# ESP32-C3_v1_0_Schematic.net
KiCad netlist of a schematic drawn in EAGLE
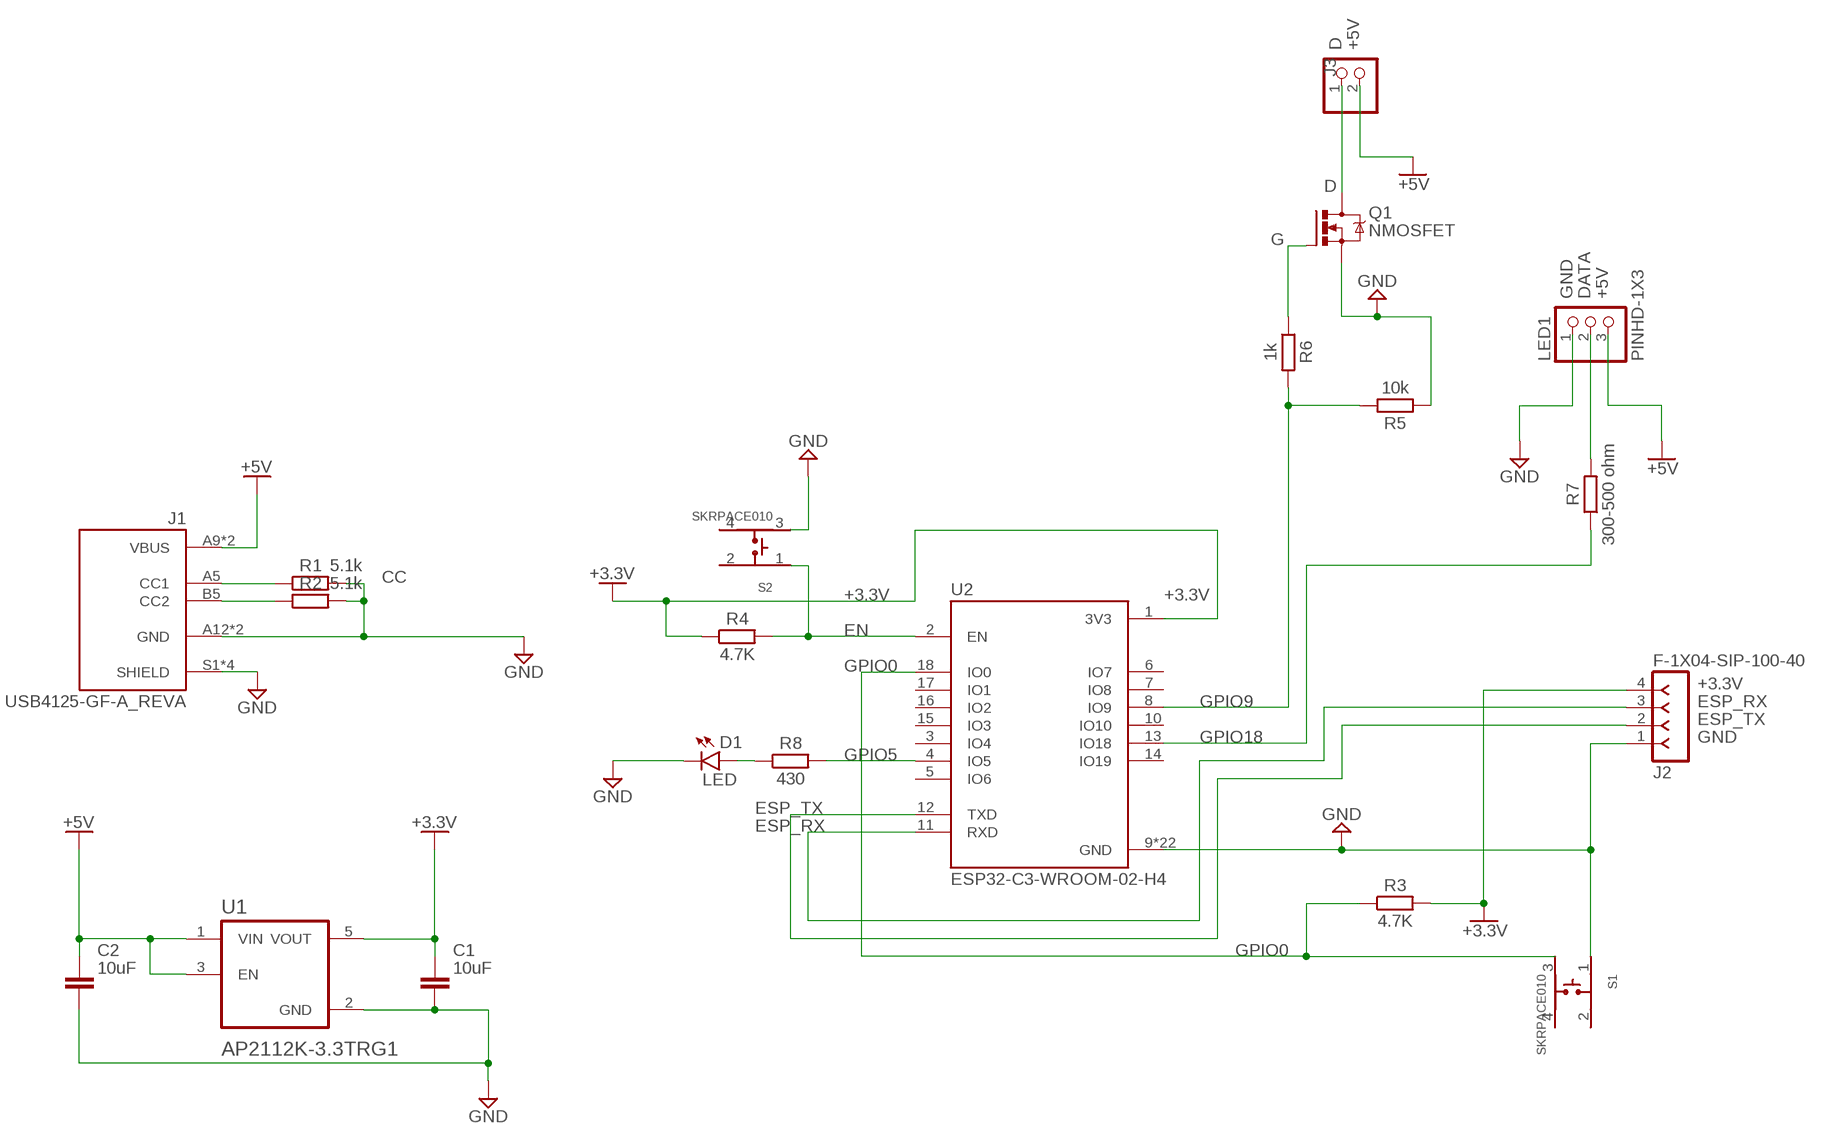
[diagram p0: schematic, sheet 1]

(export (version "E")
  (design (tool "Eeschema 10.0.6"))
  (components
    (comp (ref "C1")
      (value "10uF")
      (footprint "eagle-import:CAPC1608X85")
      (libsource (lib "eagle-import") (part "CCHIP-0603(1608-METRIC)_"))
    )
    (comp (ref "C2")
      (value "10uF")
      (footprint "eagle-import:CAPC1608X85")
      (libsource (lib "eagle-import") (part "CCHIP-0603(1608-METRIC)_"))
    )
    (comp (ref "D1")
      (value "LED")
      (footprint "eagle-import:LEDC1608X80N_FLAT-R")
      (libsource (lib "eagle-import") (part "CHIP-FLAT-R_0603-0.80MM"))
    )
    (comp (ref "J1")
      (value "USB4125-GF-A_REVA")
      (footprint "eagle-import:GCT_USB4125-GF-A_REVA")
      (fields (field (name "MF") "Global Connector Technology") (field (name "MP") "USB4125-GF-A"))
      (libsource (lib "eagle-import") (part "USB4125-GF-A_REVA"))
    )
    (comp (ref "J2")
      (value "F-1X04-SIP-100-40")
      (footprint "eagle-import:SIP-100-04-40")
      (libsource (lib "eagle-import") (part "F-1X04-SIP-100-40"))
    )
    (comp (ref "J3")
      (value "PINHD-1X2")
      (footprint "eagle-import:1X02")
      (libsource (lib "eagle-import") (part "PINHD-1X2"))
    )
    (comp (ref "LED1")
      (value "PINHD-1X3")
      (footprint "eagle-import:1X03")
      (libsource (lib "eagle-import") (part "PINHD-1X3"))
    )
    (comp (ref "Q1")
      (value "NMOSFET")
      (footprint "eagle-import:SOT23")
      (libsource (lib "eagle-import") (part "NMOSFETSOT23-GSD_"))
    )
    (comp (ref "R1")
      (value "5.1k")
      (footprint "eagle-import:RESC1608X60")
      (libsource (lib "eagle-import") (part "RCHIP-0603(1608-METRIC)_"))
    )
    (comp (ref "R2")
      (value "5.1k")
      (footprint "eagle-import:RESC1608X60")
      (libsource (lib "eagle-import") (part "RCHIP-0603(1608-METRIC)_"))
    )
    (comp (ref "R3")
      (value "4.7K")
      (footprint "eagle-import:RESC1608X60")
      (libsource (lib "eagle-import") (part "RCHIP-0603(1608-METRIC)_"))
    )
    (comp (ref "R4")
      (value "4.7K")
      (footprint "eagle-import:RESC1608X60")
      (libsource (lib "eagle-import") (part "RCHIP-0603(1608-METRIC)_"))
    )
    (comp (ref "R5")
      (value "10k")
      (footprint "eagle-import:RESC1608X60")
      (libsource (lib "eagle-import") (part "RCHIP-0603(1608-METRIC)_"))
    )
    (comp (ref "R6")
      (value "1k")
      (footprint "eagle-import:RESC1608X60")
      (libsource (lib "eagle-import") (part "RCHIP-0603(1608-METRIC)_"))
    )
    (comp (ref "R7")
      (value "300-500 ohm")
      (footprint "eagle-import:RESC1608X60")
      (libsource (lib "eagle-import") (part "RCHIP-0603(1608-METRIC)_"))
    )
    (comp (ref "R8")
      (value "430")
      (footprint "eagle-import:RESC1608X60")
      (libsource (lib "eagle-import") (part "RCHIP-0603(1608-METRIC)_"))
    )
    (comp (ref "S1")
      (value "SKRPACE010")
      (footprint "eagle-import:SW_SKRPACE010")
      (fields (field (name "MANUFACTURER") "ALPS"))
      (libsource (lib "eagle-import") (part "SKRPACE010"))
    )
    (comp (ref "S2")
      (value "SKRPACE010")
      (footprint "eagle-import:SW_SKRPACE010")
      (fields (field (name "MANUFACTURER") "ALPS"))
      (libsource (lib "eagle-import") (part "SKRPACE010"))
    )
    (comp (ref "U1")
      (value "AP2112K-3.3TRG1")
      (footprint "eagle-import:SOT95P285X140-5N")
      (fields (field (name "MANUFACTURER") "Diodes Inc."))
      (libsource (lib "eagle-import") (part "AP2112K-3.3TRG1"))
    )
    (comp (ref "U2")
      (value "ESP32-C3-WROOM-02-H4")
      (footprint "eagle-import:MODULE_ESP32-C3-WROOM-02-H4")
      (fields (field (name "MF") "Espressif Systems"))
      (libsource (lib "eagle-import") (part "ESP32-C3-WROOM-02-H4"))
    )
  )
  (nets
    (net (code "1") (name "+3.3V") (class "Default")
      (node (ref "C1") (pin "1") (pinfunction "1_1") (pintype "passive"))
      (node (ref "J2") (pin "4") (pinfunction "4_4") (pintype "passive"))
      (node (ref "R3") (pin "2") (pinfunction "2_2") (pintype "passive"))
      (node (ref "R4") (pin "1") (pinfunction "1_1") (pintype "passive"))
      (node (ref "U1") (pin "5") (pinfunction "VOUT_5") (pintype "power_in"))
      (node (ref "U2") (pin "1") (pinfunction "3V3_1") (pintype "power_in"))
    )
    (net (code "2") (name "+5V") (class "Default")
      (node (ref "C2") (pin "1") (pinfunction "1_1") (pintype "passive"))
      (node (ref "J1") (pin "A9") (pinfunction "VBUS_A9") (pintype "power_in"))
      (node (ref "J1") (pin "B9") (pinfunction "VBUS_B9") (pintype "power_in"))
      (node (ref "J3") (pin "2") (pinfunction "2_2") (pintype "passive"))
      (node (ref "LED1") (pin "3") (pinfunction "3_3") (pintype "passive"))
      (node (ref "U1") (pin "1") (pinfunction "VIN_1") (pintype "power_in"))
      (node (ref "U1") (pin "3") (pinfunction "EN_3") (pintype "input"))
    )
    (net (code "3") (name "/CC") (class "Default")
      (node (ref "J1") (pin "A5") (pinfunction "CC1_A5") (pintype "bidirectional"))
      (node (ref "R1") (pin "1") (pinfunction "1_1") (pintype "passive"))
    )
    (net (code "4") (name "/D") (class "Default")
      (node (ref "J3") (pin "1") (pinfunction "1_1") (pintype "passive"))
      (node (ref "Q1") (pin "3") (pinfunction "D_3") (pintype "passive"))
    )
    (net (code "5") (name "/DATA") (class "Default")
      (node (ref "LED1") (pin "2") (pinfunction "2_2") (pintype "passive"))
      (node (ref "R7") (pin "2") (pinfunction "2_2") (pintype "passive"))
    )
    (net (code "6") (name "/EN") (class "Default")
      (node (ref "R4") (pin "2") (pinfunction "2_2") (pintype "passive"))
      (node (ref "S2") (pin "1") (pinfunction "1_1") (pintype "bidirectional"))
      (node (ref "U2") (pin "2") (pinfunction "EN_2") (pintype "input"))
    )
    (net (code "7") (name "/ESP_RX") (class "Default")
      (node (ref "J2") (pin "3") (pinfunction "3_3") (pintype "passive"))
      (node (ref "U2") (pin "11") (pinfunction "RXD_11") (pintype "bidirectional"))
    )
    (net (code "8") (name "/ESP_TX") (class "Default")
      (node (ref "J2") (pin "2") (pinfunction "2_2") (pintype "passive"))
      (node (ref "U2") (pin "12") (pinfunction "TXD_12") (pintype "bidirectional"))
    )
    (net (code "9") (name "/G") (class "Default")
      (node (ref "Q1") (pin "1") (pinfunction "G_1") (pintype "passive"))
      (node (ref "R6") (pin "1") (pinfunction "1_1") (pintype "passive"))
    )
    (net (code "10") (name "/GPIO0") (class "Default")
      (node (ref "R3") (pin "1") (pinfunction "1_1") (pintype "passive"))
      (node (ref "S1") (pin "3") (pinfunction "3_3") (pintype "bidirectional"))
      (node (ref "U2") (pin "18") (pinfunction "IO0_18") (pintype "bidirectional"))
    )
    (net (code "11") (name "/GPIO5") (class "Default")
      (node (ref "R8") (pin "2") (pinfunction "2_2") (pintype "passive"))
      (node (ref "U2") (pin "4") (pinfunction "IO5_4") (pintype "bidirectional"))
    )
    (net (code "12") (name "/GPIO9") (class "Default")
      (node (ref "R5") (pin "2") (pinfunction "2_2") (pintype "passive"))
      (node (ref "R6") (pin "2") (pinfunction "2_2") (pintype "passive"))
      (node (ref "U2") (pin "8") (pinfunction "IO9_8") (pintype "bidirectional"))
    )
    (net (code "13") (name "/GPIO18") (class "Default")
      (node (ref "R7") (pin "1") (pinfunction "1_1") (pintype "passive"))
      (node (ref "U2") (pin "13") (pinfunction "IO18_13") (pintype "bidirectional"))
    )
    (net (code "14") (name "GND") (class "Default")
      (node (ref "C1") (pin "2") (pinfunction "2_2") (pintype "passive"))
      (node (ref "C2") (pin "2") (pinfunction "2_2") (pintype "passive"))
      (node (ref "D1") (pin "C") (pinfunction "C_C") (pintype "passive"))
      (node (ref "J1") (pin "A12") (pinfunction "GND_A12") (pintype "power_in"))
      (node (ref "J1") (pin "B12") (pinfunction "GND_B12") (pintype "power_in"))
      (node (ref "J1") (pin "S1") (pinfunction "SHIELD_S1") (pintype "passive"))
      (node (ref "J1") (pin "S2") (pinfunction "SHIELD_S2") (pintype "passive"))
      (node (ref "J1") (pin "S3") (pinfunction "SHIELD_S3") (pintype "passive"))
      (node (ref "J1") (pin "S4") (pinfunction "SHIELD_S4") (pintype "passive"))
      (node (ref "J2") (pin "1") (pinfunction "1_1") (pintype "passive"))
      (node (ref "LED1") (pin "1") (pinfunction "1_1") (pintype "passive"))
      (node (ref "Q1") (pin "2") (pinfunction "S_2") (pintype "passive"))
      (node (ref "R1") (pin "2") (pinfunction "2_2") (pintype "passive"))
      (node (ref "R2") (pin "2") (pinfunction "2_2") (pintype "passive"))
      (node (ref "R5") (pin "1") (pinfunction "1_1") (pintype "passive"))
      (node (ref "S1") (pin "1") (pinfunction "1_1") (pintype "bidirectional"))
      (node (ref "S2") (pin "3") (pinfunction "3_3") (pintype "bidirectional"))
      (node (ref "U1") (pin "2") (pinfunction "GND_2") (pintype "power_in"))
      (node (ref "U2") (pin "19") (pinfunction "GND_19") (pintype "power_in"))
      (node (ref "U2") (pin "20") (pinfunction "GND_20") (pintype "power_in"))
      (node (ref "U2") (pin "21") (pinfunction "GND_21") (pintype "power_in"))
      (node (ref "U2") (pin "22") (pinfunction "GND_22") (pintype "power_in"))
      (node (ref "U2") (pin "23") (pinfunction "GND_23") (pintype "power_in"))
      (node (ref "U2") (pin "24") (pinfunction "GND_24") (pintype "power_in"))
      (node (ref "U2") (pin "25") (pinfunction "GND_25") (pintype "power_in"))
      (node (ref "U2") (pin "26") (pinfunction "GND_26") (pintype "power_in"))
      (node (ref "U2") (pin "27") (pinfunction "GND_27") (pintype "power_in"))
      (node (ref "U2") (pin "28") (pinfunction "GND_28") (pintype "power_in"))
      (node (ref "U2") (pin "29") (pinfunction "GND_29") (pintype "power_in"))
      (node (ref "U2") (pin "30") (pinfunction "GND_30") (pintype "power_in"))
      (node (ref "U2") (pin "31") (pinfunction "GND_31") (pintype "power_in"))
      (node (ref "U2") (pin "32") (pinfunction "GND_32") (pintype "power_in"))
      (node (ref "U2") (pin "33") (pinfunction "GND_33") (pintype "power_in"))
      (node (ref "U2") (pin "34") (pinfunction "GND_34") (pintype "power_in"))
      (node (ref "U2") (pin "35") (pinfunction "GND_35") (pintype "power_in"))
      (node (ref "U2") (pin "36") (pinfunction "GND_36") (pintype "power_in"))
      (node (ref "U2") (pin "37") (pinfunction "GND_37") (pintype "power_in"))
      (node (ref "U2") (pin "38") (pinfunction "GND_38") (pintype "power_in"))
      (node (ref "U2") (pin "39") (pinfunction "GND_39") (pintype "power_in"))
      (node (ref "U2") (pin "9") (pinfunction "GND_9") (pintype "power_in"))
    )
    (net (code "15") (name "Net-(D1-PadA)") (class "Default")
      (node (ref "D1") (pin "A") (pinfunction "A_A") (pintype "passive"))
      (node (ref "R8") (pin "1") (pinfunction "1_1") (pintype "passive"))
    )
    (net (code "16") (name "Net-(J1-CC2)") (class "Default")
      (node (ref "J1") (pin "B5") (pinfunction "CC2_B5") (pintype "bidirectional"))
      (node (ref "R2") (pin "1") (pinfunction "1_1") (pintype "passive"))
    )
    (net (code "17") (name "unconnected-(S1-Pad2)") (class "Default")
      (node (ref "S1") (pin "2") (pinfunction "2_2") (pintype "bidirectional"))
    )
    (net (code "18") (name "unconnected-(S1-Pad4)") (class "Default")
      (node (ref "S1") (pin "4") (pinfunction "4_4") (pintype "bidirectional"))
    )
    (net (code "19") (name "unconnected-(S2-Pad2)") (class "Default")
      (node (ref "S2") (pin "2") (pinfunction "2_2") (pintype "bidirectional"))
    )
    (net (code "20") (name "unconnected-(S2-Pad4)") (class "Default")
      (node (ref "S2") (pin "4") (pinfunction "4_4") (pintype "bidirectional"))
    )
    (net (code "21") (name "unconnected-(U2-IO1-Pad17)") (class "Default")
      (node (ref "U2") (pin "17") (pinfunction "IO1_17") (pintype "bidirectional"))
    )
    (net (code "22") (name "unconnected-(U2-IO2-Pad16)") (class "Default")
      (node (ref "U2") (pin "16") (pinfunction "IO2_16") (pintype "bidirectional"))
    )
    (net (code "23") (name "unconnected-(U2-IO3-Pad15)") (class "Default")
      (node (ref "U2") (pin "15") (pinfunction "IO3_15") (pintype "bidirectional"))
    )
    (net (code "24") (name "unconnected-(U2-IO4-Pad3)") (class "Default")
      (node (ref "U2") (pin "3") (pinfunction "IO4_3") (pintype "bidirectional"))
    )
    (net (code "25") (name "unconnected-(U2-IO6-Pad5)") (class "Default")
      (node (ref "U2") (pin "5") (pinfunction "IO6_5") (pintype "bidirectional"))
    )
    (net (code "26") (name "unconnected-(U2-IO7-Pad6)") (class "Default")
      (node (ref "U2") (pin "6") (pinfunction "IO7_6") (pintype "bidirectional"))
    )
    (net (code "27") (name "unconnected-(U2-IO8-Pad7)") (class "Default")
      (node (ref "U2") (pin "7") (pinfunction "IO8_7") (pintype "bidirectional"))
    )
    (net (code "28") (name "unconnected-(U2-IO10-Pad10)") (class "Default")
      (node (ref "U2") (pin "10") (pinfunction "IO10_10") (pintype "bidirectional"))
    )
    (net (code "29") (name "unconnected-(U2-IO19-Pad14)") (class "Default")
      (node (ref "U2") (pin "14") (pinfunction "IO19_14") (pintype "bidirectional"))
    )
  )
)
